# daughterBoard.net
KiCad netlist of a schematic drawn in EAGLE
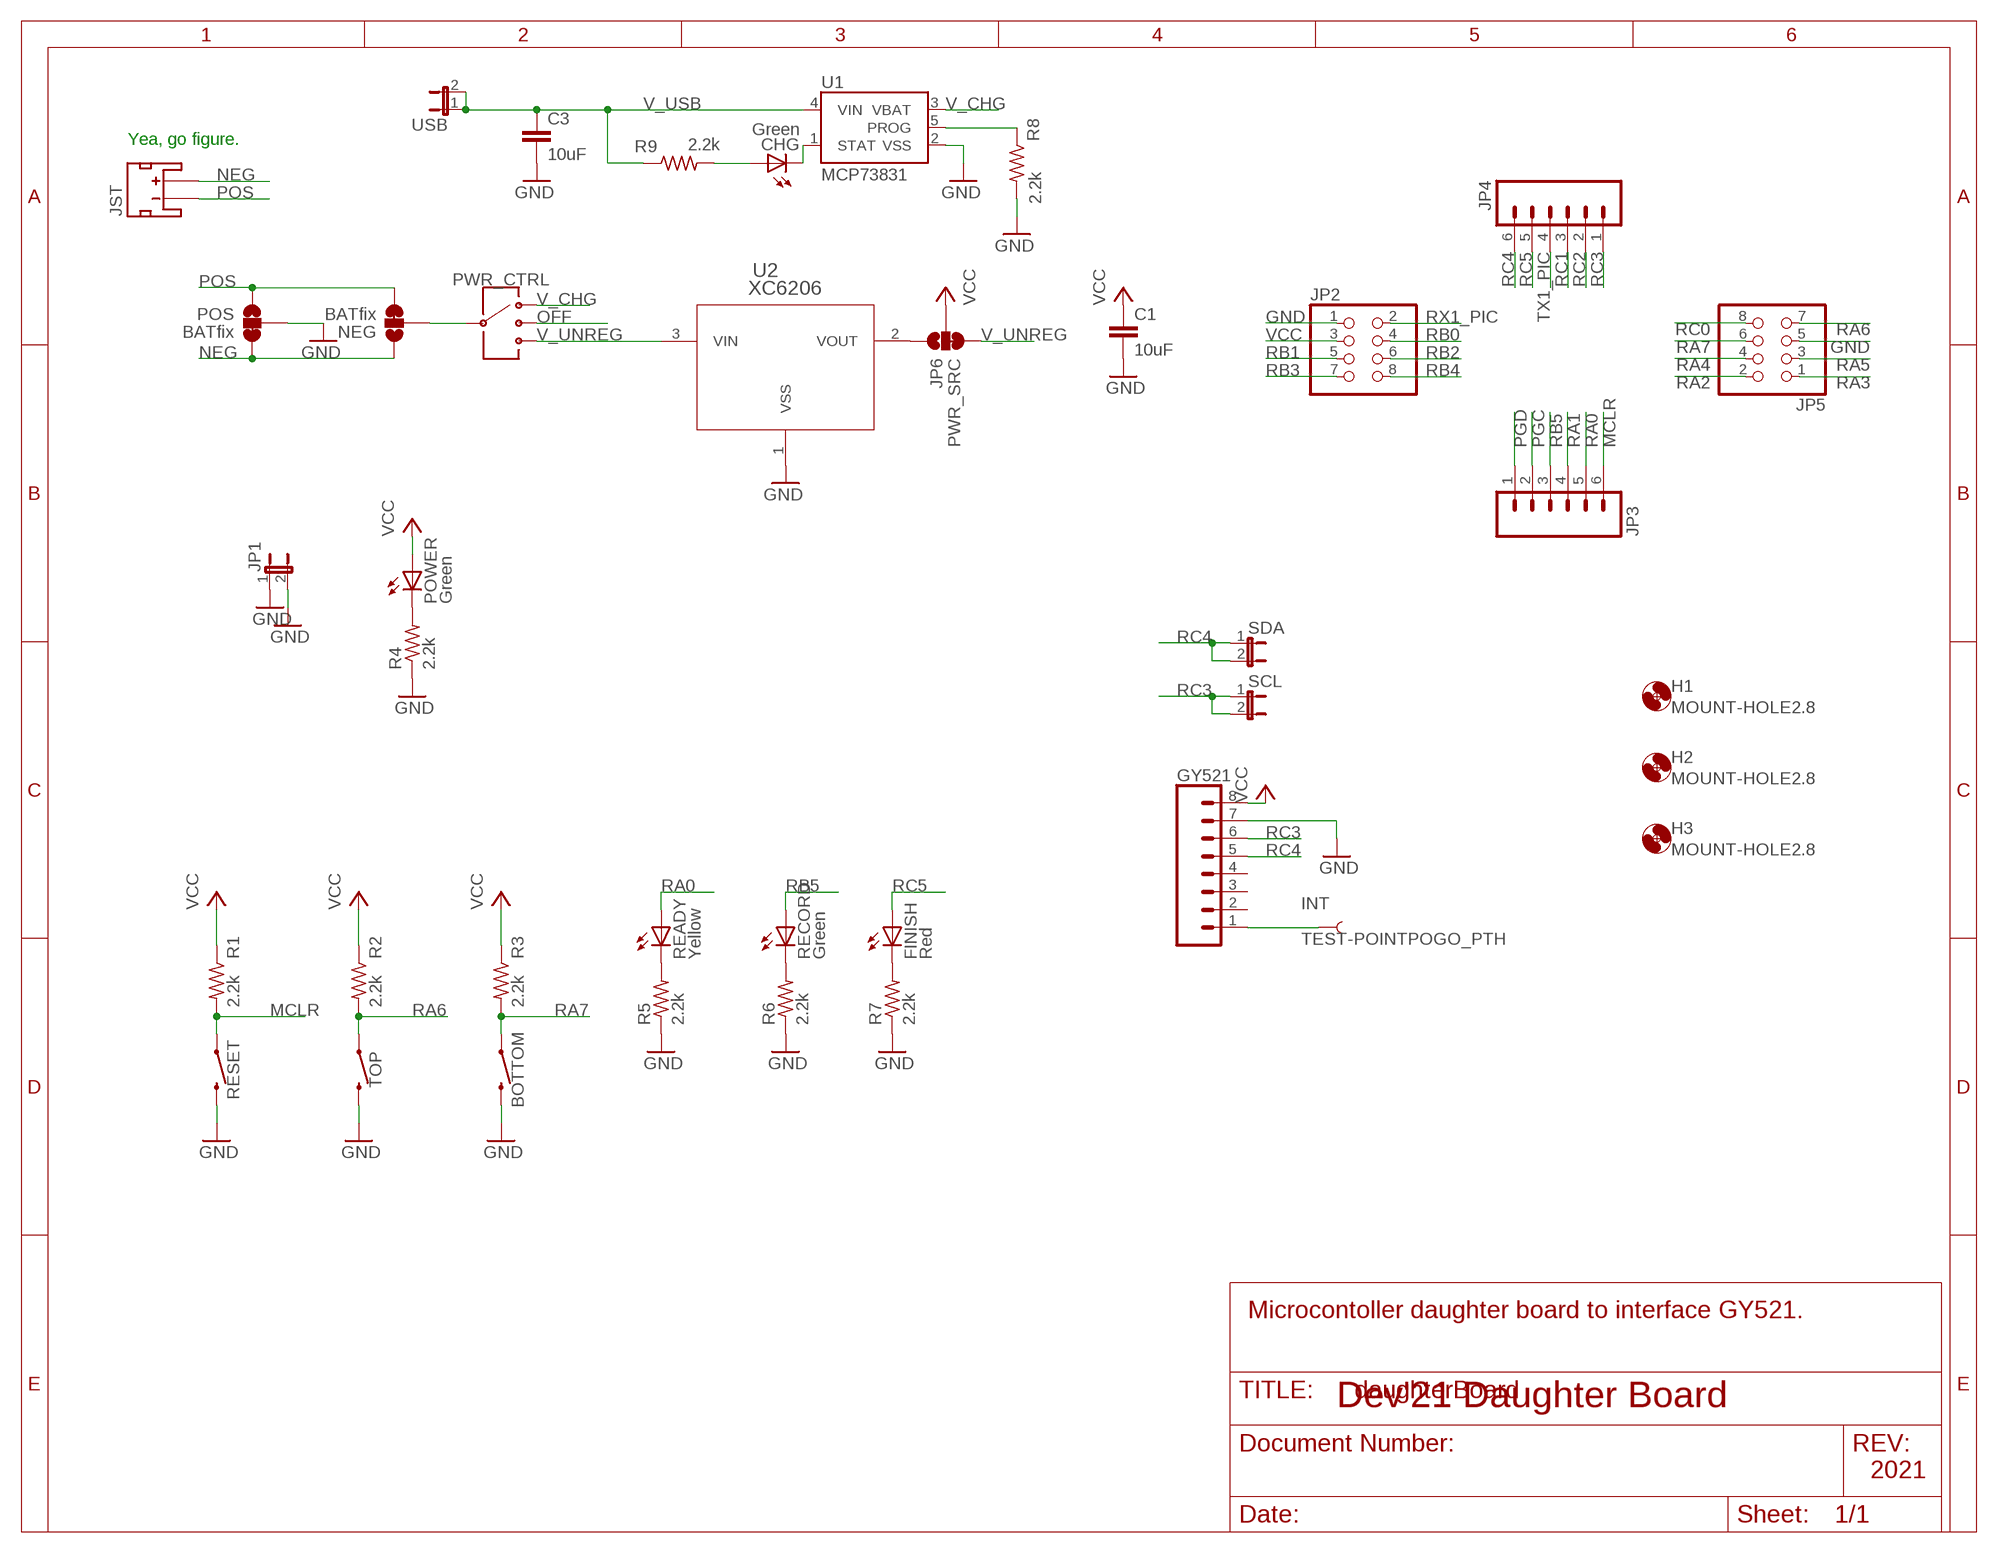
[diagram p0: schematic, sheet 1]

(export (version "E")
  (design (tool "Eeschema 10.0.6"))
  (components
    (comp (ref "BOTTOM")
      (value "BOTTOM")
      (footprint "eagle-import:TACTILE_SWITCH_SMD_5.2MM")
      (libsource (lib "eagle-import") (part "MOMENTARY-SWITCH-SPST-SMD-5.2MM"))
    )
    (comp (ref "C1")
      (value "10uF")
      (footprint "eagle-import:C1206")
      (libsource (lib "eagle-import") (part "C-EUC1206"))
    )
    (comp (ref "C3")
      (value "10uF")
      (footprint "eagle-import:C1206")
      (libsource (lib "eagle-import") (part "C-EUC1206"))
    )
    (comp (ref "CHG")
      (value "Green")
      (footprint "eagle-import:LED-1206")
      (libsource (lib "eagle-import") (part "LED1206"))
    )
    (comp (ref "FINISH")
      (value "Red")
      (footprint "eagle-import:LED-1206")
      (libsource (lib "eagle-import") (part "LED1206"))
    )
    (comp (ref "GY521")
      (value "CONN_08LOCK_LONGPADS")
      (footprint "eagle-import:1X08_LOCK_LONGPADS")
      (libsource (lib "eagle-import") (part "CONN_08LOCK_LONGPADS"))
    )
    (comp (ref "H1")
      (value "MOUNT-HOLE2.8")
      (footprint "eagle-import:2,8")
      (libsource (lib "eagle-import") (part "MOUNT-HOLE2.8"))
    )
    (comp (ref "H2")
      (value "MOUNT-HOLE2.8")
      (footprint "eagle-import:2,8")
      (libsource (lib "eagle-import") (part "MOUNT-HOLE2.8"))
    )
    (comp (ref "H3")
      (value "MOUNT-HOLE2.8")
      (footprint "eagle-import:2,8")
      (libsource (lib "eagle-import") (part "MOUNT-HOLE2.8"))
    )
    (comp (ref "INT")
      (value "TEST-POINTPOGO_PTH")
      (footprint "eagle-import:1X01_NO_SILK")
      (libsource (lib "eagle-import") (part "TEST-POINTPOGO_PTH"))
    )
    (comp (ref "JP1")
      (value "JP1E")
      (footprint "eagle-import:JP1")
      (libsource (lib "eagle-import") (part "JP1E"))
    )
    (comp (ref "JP2")
      (value "PINHD-2X4")
      (footprint "eagle-import:2X04")
      (libsource (lib "eagle-import") (part "PINHD-2X4"))
    )
    (comp (ref "JP3")
      (value "M06LOCK")
      (footprint "eagle-import:1X06_LOCK")
      (libsource (lib "eagle-import") (part "M06LOCK"))
    )
    (comp (ref "JP4")
      (value "M06LOCK")
      (footprint "eagle-import:1X06_LOCK")
      (libsource (lib "eagle-import") (part "M06LOCK"))
    )
    (comp (ref "JP5")
      (value "PINHD-2X4")
      (footprint "eagle-import:2X04")
      (libsource (lib "eagle-import") (part "PINHD-2X4"))
    )
    (comp (ref "JP6")
      (value "PWR_SRC")
      (footprint "eagle-import:SMT-JUMPER_3_1-NC_TRACE_SILK")
      (libsource (lib "eagle-import") (part "JUMPER-SMT_3_1-NC_TRACE_SILK"))
    )
    (comp (ref "JST")
      (value "JST_2MM_MALE")
      (footprint "eagle-import:JST-2-SMD")
      (libsource (lib "eagle-import") (part "JST_2MM_MALE"))
    )
    (comp (ref "NEG")
      (value "BATfix")
      (footprint "eagle-import:SMT-JUMPER_3_1-NC_TRACE_SILK")
      (libsource (lib "eagle-import") (part "JUMPER-SMT_3_1-NC_TRACE_SILK"))
    )
    (comp (ref "POS")
      (value "BATfix")
      (footprint "eagle-import:SMT-JUMPER_3_1-NC_TRACE_SILK")
      (libsource (lib "eagle-import") (part "JUMPER-SMT_3_1-NC_TRACE_SILK"))
    )
    (comp (ref "POWER")
      (value "Green")
      (footprint "eagle-import:LED-1206")
      (libsource (lib "eagle-import") (part "LED1206"))
    )
    (comp (ref "PWR_CTRL")
      (value "SWITCH-SP3T-SMD")
      (footprint "eagle-import:SWITCH_SP3T_SMD")
      (libsource (lib "eagle-import") (part "SWITCH-SP3T-SMD"))
    )
    (comp (ref "R1")
      (value "2.2k")
      (footprint "eagle-import:R1206")
      (libsource (lib "eagle-import") (part "R-US_R1206"))
    )
    (comp (ref "R2")
      (value "2.2k")
      (footprint "eagle-import:R1206")
      (libsource (lib "eagle-import") (part "R-US_R1206"))
    )
    (comp (ref "R3")
      (value "2.2k")
      (footprint "eagle-import:R1206")
      (libsource (lib "eagle-import") (part "R-US_R1206"))
    )
    (comp (ref "R4")
      (value "2.2k")
      (footprint "eagle-import:R1206")
      (libsource (lib "eagle-import") (part "R-US_R1206"))
    )
    (comp (ref "R5")
      (value "2.2k")
      (footprint "eagle-import:R1206")
      (libsource (lib "eagle-import") (part "R-US_R1206"))
    )
    (comp (ref "R6")
      (value "2.2k")
      (footprint "eagle-import:R1206")
      (libsource (lib "eagle-import") (part "R-US_R1206"))
    )
    (comp (ref "R7")
      (value "2.2k")
      (footprint "eagle-import:R1206")
      (libsource (lib "eagle-import") (part "R-US_R1206"))
    )
    (comp (ref "R8")
      (value "2.2k")
      (footprint "eagle-import:R1206")
      (libsource (lib "eagle-import") (part "R-US_R1206"))
    )
    (comp (ref "R9")
      (value "2.2k")
      (footprint "eagle-import:R1206")
      (libsource (lib "eagle-import") (part "R-US_R1206"))
    )
    (comp (ref "READY")
      (value "Yellow")
      (footprint "eagle-import:LED-1206")
      (libsource (lib "eagle-import") (part "LED1206"))
    )
    (comp (ref "RECORD")
      (value "Green")
      (footprint "eagle-import:LED-1206")
      (libsource (lib "eagle-import") (part "LED1206"))
    )
    (comp (ref "RESET")
      (value "RESET")
      (footprint "eagle-import:TACTILE_SWITCH_SMD_5.2MM")
      (libsource (lib "eagle-import") (part "MOMENTARY-SWITCH-SPST-SMD-5.2MM"))
    )
    (comp (ref "SCL")
      (value "JUMPER-2PTH_LOCK")
      (footprint "eagle-import:1X02_LOCK")
      (libsource (lib "eagle-import") (part "JUMPER-2PTH_LOCK"))
    )
    (comp (ref "SDA")
      (value "JUMPER-2PTH_LOCK")
      (footprint "eagle-import:1X02_LOCK")
      (libsource (lib "eagle-import") (part "JUMPER-2PTH_LOCK"))
    )
    (comp (ref "TOP")
      (value "TOP")
      (footprint "eagle-import:TACTILE_SWITCH_SMD_5.2MM")
      (libsource (lib "eagle-import") (part "MOMENTARY-SWITCH-SPST-SMD-5.2MM"))
    )
    (comp (ref "U1")
      (value "MCP73831")
      (footprint "eagle-import:SOT23-5")
      (libsource (lib "eagle-import") (part "MCP73831"))
    )
    (comp (ref "U2")
      (value "XC6206")
      (footprint "eagle-import:SOT-23_TOR-M")
      (fields
        (field (name "MANUFACTURER_PART_NUMBER") "XC6206P332MR-G")
        (field (name "COPYRIGHT") "Copyright (C) 2021 Ultra Librarian. All rights reserved.")
      )
      (libsource (lib "eagle-import") (part "XC6206P332MR-GSOT-23_TOR-M"))
    )
    (comp (ref "USB")
      (value "JUMPER-2PTH_LOCK")
      (footprint "eagle-import:1X02_LOCK")
      (libsource (lib "eagle-import") (part "JUMPER-2PTH_LOCK"))
    )
  )
  (nets
    (net (code "1") (name "/MCLR") (class "Default")
      (node (ref "JP3") (pin "6") (pinfunction "6_6") (pintype "passive"))
      (node (ref "R1") (pin "2") (pinfunction "2_2") (pintype "passive"))
      (node (ref "RESET") (pin "1") (pinfunction "1_1") (pintype "passive"))
    )
    (net (code "2") (name "/NEG") (class "Default")
      (node (ref "JST") (pin "2") (pinfunction "+_2") (pintype "bidirectional"))
      (node (ref "NEG") (pin "1") (pinfunction "1_1") (pintype "passive"))
      (node (ref "POS") (pin "3") (pinfunction "3_3") (pintype "passive"))
    )
    (net (code "3") (name "/OFF") (class "Default")
      (node (ref "PWR_CTRL") (pin "2") (pinfunction "2_2") (pintype "bidirectional"))
    )
    (net (code "4") (name "/PGC") (class "Default")
      (node (ref "JP3") (pin "2") (pinfunction "2_2") (pintype "passive"))
    )
    (net (code "5") (name "/PGD") (class "Default")
      (node (ref "JP3") (pin "1") (pinfunction "1_1") (pintype "passive"))
    )
    (net (code "6") (name "/POS") (class "Default")
      (node (ref "JST") (pin "1") (pinfunction "-_1") (pintype "bidirectional"))
      (node (ref "NEG") (pin "3") (pinfunction "3_3") (pintype "passive"))
      (node (ref "POS") (pin "1") (pinfunction "1_1") (pintype "passive"))
    )
    (net (code "7") (name "/RA0") (class "Default")
      (node (ref "JP3") (pin "5") (pinfunction "5_5") (pintype "passive"))
      (node (ref "READY") (pin "A") (pinfunction "A_A") (pintype "passive"))
    )
    (net (code "8") (name "/RA1") (class "Default")
      (node (ref "JP3") (pin "4") (pinfunction "4_4") (pintype "passive"))
    )
    (net (code "9") (name "/RA2") (class "Default")
      (node (ref "JP5") (pin "2") (pinfunction "2_2") (pintype "passive"))
    )
    (net (code "10") (name "/RA3") (class "Default")
      (node (ref "JP5") (pin "1") (pinfunction "1_1") (pintype "passive"))
    )
    (net (code "11") (name "/RA4") (class "Default")
      (node (ref "JP5") (pin "4") (pinfunction "4_4") (pintype "passive"))
    )
    (net (code "12") (name "/RA5") (class "Default")
      (node (ref "JP5") (pin "3") (pinfunction "3_3") (pintype "passive"))
    )
    (net (code "13") (name "/RA6") (class "Default")
      (node (ref "JP5") (pin "7") (pinfunction "7_7") (pintype "passive"))
      (node (ref "R2") (pin "2") (pinfunction "2_2") (pintype "passive"))
      (node (ref "TOP") (pin "1") (pinfunction "1_1") (pintype "passive"))
    )
    (net (code "14") (name "/RA7") (class "Default")
      (node (ref "BOTTOM") (pin "1") (pinfunction "1_1") (pintype "passive"))
      (node (ref "JP5") (pin "6") (pinfunction "6_6") (pintype "passive"))
      (node (ref "R3") (pin "2") (pinfunction "2_2") (pintype "passive"))
    )
    (net (code "15") (name "/RB0") (class "Default")
      (node (ref "JP2") (pin "4") (pinfunction "4_4") (pintype "passive"))
    )
    (net (code "16") (name "/RB1") (class "Default")
      (node (ref "JP2") (pin "5") (pinfunction "5_5") (pintype "passive"))
    )
    (net (code "17") (name "/RB2") (class "Default")
      (node (ref "JP2") (pin "6") (pinfunction "6_6") (pintype "passive"))
    )
    (net (code "18") (name "/RB3") (class "Default")
      (node (ref "JP2") (pin "7") (pinfunction "7_7") (pintype "passive"))
    )
    (net (code "19") (name "/RB4") (class "Default")
      (node (ref "JP2") (pin "8") (pinfunction "8_8") (pintype "passive"))
    )
    (net (code "20") (name "/RB5") (class "Default")
      (node (ref "JP3") (pin "3") (pinfunction "3_3") (pintype "passive"))
      (node (ref "RECORD") (pin "A") (pinfunction "A_A") (pintype "passive"))
    )
    (net (code "21") (name "/RC0") (class "Default")
      (node (ref "JP5") (pin "8") (pinfunction "8_8") (pintype "passive"))
    )
    (net (code "22") (name "/RC1") (class "Default")
      (node (ref "JP4") (pin "3") (pinfunction "3_3") (pintype "passive"))
    )
    (net (code "23") (name "/RC2") (class "Default")
      (node (ref "JP4") (pin "2") (pinfunction "2_2") (pintype "passive"))
    )
    (net (code "24") (name "/RC3") (class "Default")
      (node (ref "GY521") (pin "6") (pinfunction "6_6") (pintype "passive"))
      (node (ref "JP4") (pin "1") (pinfunction "1_1") (pintype "passive"))
      (node (ref "SCL") (pin "1") (pinfunction "1_1") (pintype "passive"))
      (node (ref "SCL") (pin "2") (pinfunction "2_2") (pintype "passive"))
    )
    (net (code "25") (name "/RC4") (class "Default")
      (node (ref "GY521") (pin "5") (pinfunction "5_5") (pintype "passive"))
      (node (ref "JP4") (pin "6") (pinfunction "6_6") (pintype "passive"))
      (node (ref "SDA") (pin "1") (pinfunction "1_1") (pintype "passive"))
      (node (ref "SDA") (pin "2") (pinfunction "2_2") (pintype "passive"))
    )
    (net (code "26") (name "/RC5") (class "Default")
      (node (ref "FINISH") (pin "A") (pinfunction "A_A") (pintype "passive"))
      (node (ref "JP4") (pin "5") (pinfunction "5_5") (pintype "passive"))
    )
    (net (code "27") (name "/RX1_PIC") (class "Default")
      (node (ref "JP2") (pin "2") (pinfunction "2_2") (pintype "passive"))
    )
    (net (code "28") (name "/TX1_PIC") (class "Default")
      (node (ref "JP4") (pin "4") (pinfunction "4_4") (pintype "passive"))
    )
    (net (code "29") (name "/V_CHG") (class "Default")
      (node (ref "PWR_CTRL") (pin "1") (pinfunction "1_1") (pintype "bidirectional"))
      (node (ref "U1") (pin "3") (pinfunction "VBAT_3") (pintype "power_in"))
    )
    (net (code "30") (name "/V_UNREG") (class "Default")
      (node (ref "JP6") (pin "3") (pinfunction "3_3") (pintype "passive"))
      (node (ref "PWR_CTRL") (pin "4") (pinfunction "4_4") (pintype "bidirectional"))
      (node (ref "U2") (pin "3") (pinfunction "VIN_3") (pintype "power_in"))
    )
    (net (code "31") (name "/V_USB") (class "Default")
      (node (ref "C3") (pin "1") (pinfunction "1_1") (pintype "passive"))
      (node (ref "R9") (pin "1") (pinfunction "1_1") (pintype "passive"))
      (node (ref "U1") (pin "4") (pinfunction "VIN_4") (pintype "power_in"))
      (node (ref "USB") (pin "1") (pinfunction "1_1") (pintype "passive"))
      (node (ref "USB") (pin "2") (pinfunction "2_2") (pintype "passive"))
    )
    (net (code "32") (name "GND") (class "Default")
      (node (ref "BOTTOM") (pin "3") (pinfunction "2_3") (pintype "passive"))
      (node (ref "C1") (pin "2") (pinfunction "2_2") (pintype "passive"))
      (node (ref "C3") (pin "2") (pinfunction "2_2") (pintype "passive"))
      (node (ref "GY521") (pin "7") (pinfunction "7_7") (pintype "passive"))
      (node (ref "JP1") (pin "1") (pinfunction "1_1") (pintype "passive"))
      (node (ref "JP1") (pin "2") (pinfunction "2_2") (pintype "passive"))
      (node (ref "JP2") (pin "1") (pinfunction "1_1") (pintype "passive"))
      (node (ref "JP5") (pin "5") (pinfunction "5_5") (pintype "passive"))
      (node (ref "POS") (pin "2") (pinfunction "2_2") (pintype "passive"))
      (node (ref "R4") (pin "1") (pinfunction "1_1") (pintype "passive"))
      (node (ref "R5") (pin "1") (pinfunction "1_1") (pintype "passive"))
      (node (ref "R6") (pin "1") (pinfunction "1_1") (pintype "passive"))
      (node (ref "R7") (pin "1") (pinfunction "1_1") (pintype "passive"))
      (node (ref "R8") (pin "2") (pinfunction "2_2") (pintype "passive"))
      (node (ref "RESET") (pin "3") (pinfunction "2_3") (pintype "passive"))
      (node (ref "TOP") (pin "3") (pinfunction "2_3") (pintype "passive"))
      (node (ref "U1") (pin "2") (pinfunction "VSS_2") (pintype "power_in"))
      (node (ref "U2") (pin "1") (pinfunction "VSS_1") (pintype "passive"))
    )
    (net (code "33") (name "Net-(CHG-PadA)") (class "Default")
      (node (ref "CHG") (pin "A") (pinfunction "A_A") (pintype "passive"))
      (node (ref "R9") (pin "2") (pinfunction "2_2") (pintype "passive"))
    )
    (net (code "34") (name "Net-(FINISH-PadC)") (class "Default")
      (node (ref "FINISH") (pin "C") (pinfunction "C_C") (pintype "passive"))
      (node (ref "R7") (pin "2") (pinfunction "2_2") (pintype "passive"))
    )
    (net (code "35") (name "Net-(GY521-Pad1)") (class "Default")
      (node (ref "GY521") (pin "1") (pinfunction "1_1") (pintype "passive"))
      (node (ref "INT") (pin "1") (pinfunction "1_1") (pintype "bidirectional"))
    )
    (net (code "36") (name "Net-(NEG-Pad2)") (class "Default")
      (node (ref "NEG") (pin "2") (pinfunction "2_2") (pintype "passive"))
      (node (ref "PWR_CTRL") (pin "3") (pinfunction "3_3") (pintype "bidirectional"))
    )
    (net (code "37") (name "Net-(POWER-PadC)") (class "Default")
      (node (ref "POWER") (pin "C") (pinfunction "C_C") (pintype "passive"))
      (node (ref "R4") (pin "2") (pinfunction "2_2") (pintype "passive"))
    )
    (net (code "38") (name "Net-(R5-Pad2)") (class "Default")
      (node (ref "R5") (pin "2") (pinfunction "2_2") (pintype "passive"))
      (node (ref "READY") (pin "C") (pinfunction "C_C") (pintype "passive"))
    )
    (net (code "39") (name "Net-(R6-Pad2)") (class "Default")
      (node (ref "R6") (pin "2") (pinfunction "2_2") (pintype "passive"))
      (node (ref "RECORD") (pin "C") (pinfunction "C_C") (pintype "passive"))
    )
    (net (code "40") (name "Net-(U1-PROG)") (class "Default")
      (node (ref "R8") (pin "1") (pinfunction "1_1") (pintype "passive"))
      (node (ref "U1") (pin "5") (pinfunction "PROG_5") (pintype "input"))
    )
    (net (code "41") (name "Net-(U1-STAT)") (class "Default")
      (node (ref "CHG") (pin "C") (pinfunction "C_C") (pintype "passive"))
      (node (ref "U1") (pin "1") (pinfunction "STAT_1") (pintype "output"))
    )
    (net (code "42") (name "Net-(U2-VOUT)") (class "Default")
      (node (ref "JP6") (pin "1") (pinfunction "1_1") (pintype "passive"))
      (node (ref "U2") (pin "2") (pinfunction "VOUT_2") (pintype "output"))
    )
    (net (code "43") (name "VCC") (class "Default")
      (node (ref "C1") (pin "1") (pinfunction "1_1") (pintype "passive"))
      (node (ref "GY521") (pin "8") (pinfunction "8_8") (pintype "passive"))
      (node (ref "JP2") (pin "3") (pinfunction "3_3") (pintype "passive"))
      (node (ref "JP6") (pin "2") (pinfunction "2_2") (pintype "passive"))
      (node (ref "POWER") (pin "A") (pinfunction "A_A") (pintype "passive"))
      (node (ref "R1") (pin "1") (pinfunction "1_1") (pintype "passive"))
      (node (ref "R2") (pin "1") (pinfunction "1_1") (pintype "passive"))
      (node (ref "R3") (pin "1") (pinfunction "1_1") (pintype "passive"))
    )
    (net (code "44") (name "unconnected-(GY521-Pad2)") (class "Default")
      (node (ref "GY521") (pin "2") (pinfunction "2_2") (pintype "passive"))
    )
    (net (code "45") (name "unconnected-(GY521-Pad3)") (class "Default")
      (node (ref "GY521") (pin "3") (pinfunction "3_3") (pintype "passive"))
    )
    (net (code "46") (name "unconnected-(GY521-Pad4)") (class "Default")
      (node (ref "GY521") (pin "4") (pinfunction "4_4") (pintype "passive"))
    )
    (net (code "47") (name "unconnected-(JST-PAD1-PadNC1)") (class "Default")
      (node (ref "JST") (pin "NC1") (pinfunction "PAD1_NC1") (pintype "bidirectional"))
    )
    (net (code "48") (name "unconnected-(JST-PAD2-PadNC2)") (class "Default")
      (node (ref "JST") (pin "NC2") (pinfunction "PAD2_NC2") (pintype "bidirectional"))
    )
  )
)
